# ramanPi_imagingBoard.net
KiCad netlist of a schematic drawn in EAGLE
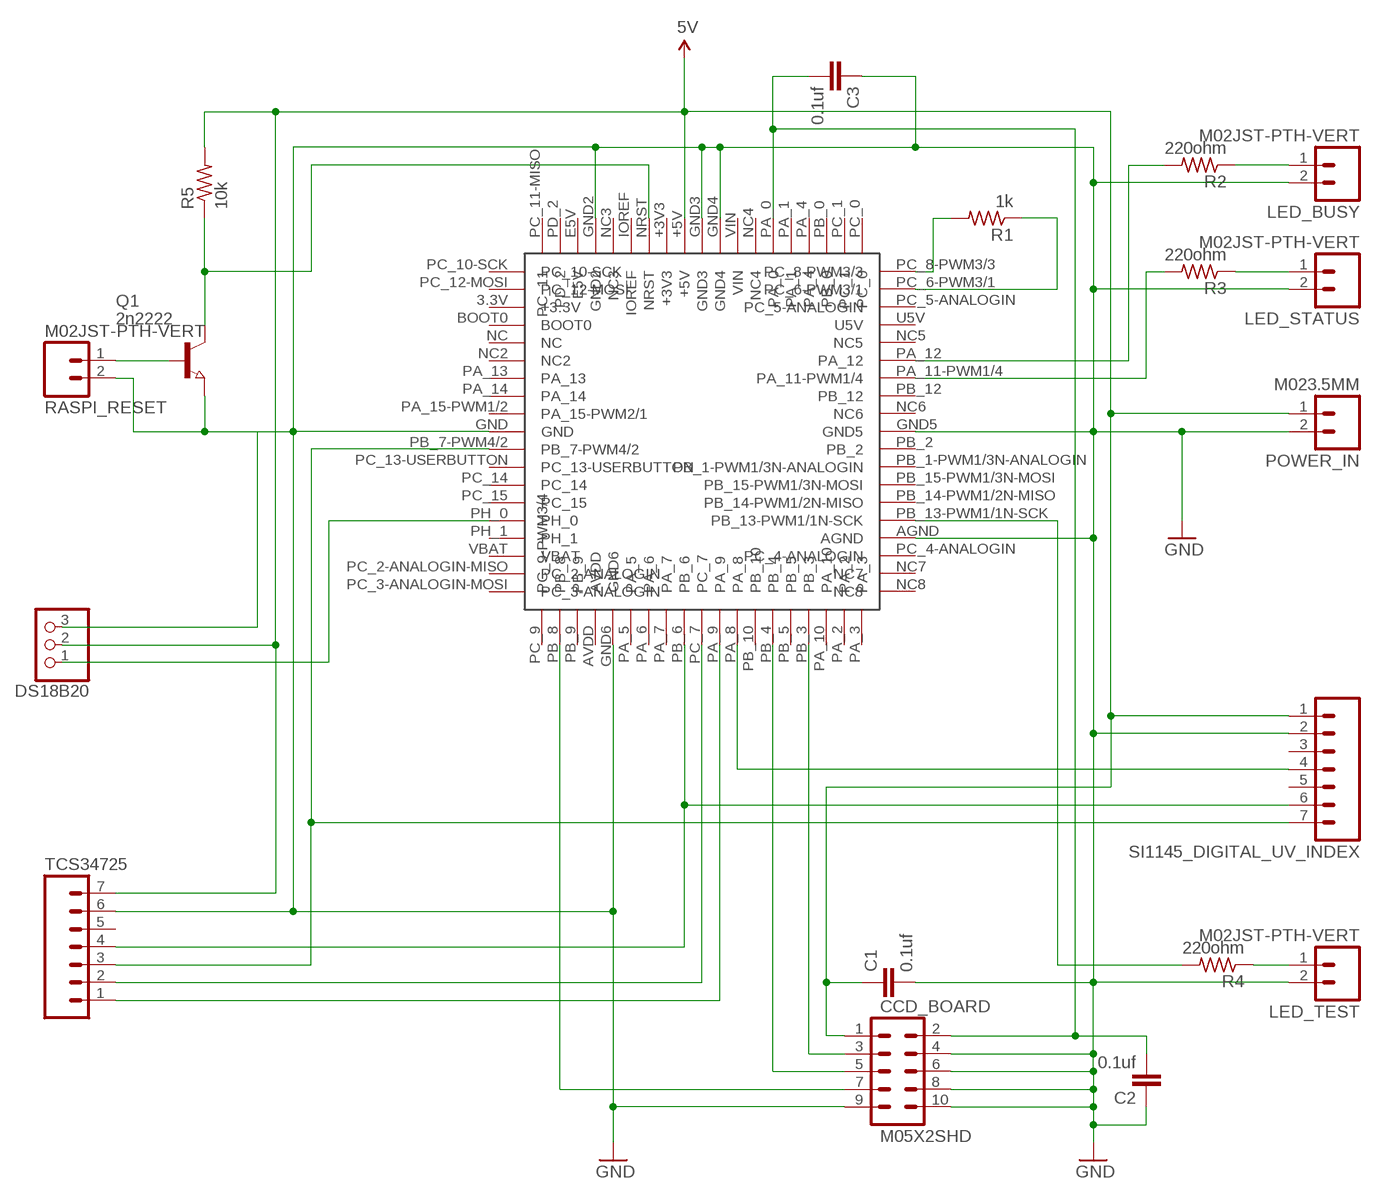
[diagram p0: schematic, sheet 1]

(export (version "E")
  (design (tool "Eeschema 10.0.6"))
  (components
    (comp (ref "C1")
      (value "0.1uf")
      (footprint "eagle-import:1210")
      (libsource (lib "eagle-import") (part "CAP1210"))
    )
    (comp (ref "C2")
      (value "0.1uf")
      (footprint "eagle-import:1210")
      (libsource (lib "eagle-import") (part "CAP1210"))
    )
    (comp (ref "C3")
      (value "0.1uf")
      (footprint "eagle-import:1210")
      (libsource (lib "eagle-import") (part "CAP1210"))
    )
    (comp (ref "CCD_BOARD")
      (value "M05X2SHD")
      (footprint "eagle-import:2X5-SHROUDED")
      (libsource (lib "eagle-import") (part "M05X2SHD"))
    )
    (comp (ref "DS18B20")
      (value "PINHD-1X3")
      (footprint "eagle-import:1X03")
      (libsource (lib "eagle-import") (part "PINHD-1X3"))
    )
    (comp (ref "LED_BUSY")
      (value "M02JST-PTH-VERT")
      (footprint "eagle-import:JST-2-PTH-VERT")
      (libsource (lib "eagle-import") (part "M02JST-PTH-VERT"))
    )
    (comp (ref "LED_STATUS")
      (value "M02JST-PTH-VERT")
      (footprint "eagle-import:JST-2-PTH-VERT")
      (libsource (lib "eagle-import") (part "M02JST-PTH-VERT"))
    )
    (comp (ref "LED_TEST")
      (value "M02JST-PTH-VERT")
      (footprint "eagle-import:JST-2-PTH-VERT")
      (libsource (lib "eagle-import") (part "M02JST-PTH-VERT"))
    )
    (comp (ref "POWER_IN")
      (value "M023.5MM")
      (footprint "eagle-import:SCREWTERMINAL-3.5MM-2")
      (libsource (lib "eagle-import") (part "M023.5MM"))
    )
    (comp (ref "Q1")
      (value "2n2222")
      (footprint "eagle-import:SOT23")
      (libsource (lib "eagle-import") (part "NPN-TRANSISTOR_SOT23"))
    )
    (comp (ref "R1")
      (value "1k")
      (footprint "eagle-import:M1206")
      (libsource (lib "eagle-import") (part "R-US_M1206"))
    )
    (comp (ref "R2")
      (value "220ohm")
      (footprint "eagle-import:M1206")
      (libsource (lib "eagle-import") (part "R-US_M1206"))
    )
    (comp (ref "R3")
      (value "220ohm")
      (footprint "eagle-import:M1206")
      (libsource (lib "eagle-import") (part "R-US_M1206"))
    )
    (comp (ref "R4")
      (value "220ohm")
      (footprint "eagle-import:M1206")
      (libsource (lib "eagle-import") (part "R-US_M1206"))
    )
    (comp (ref "R5")
      (value "10k")
      (footprint "eagle-import:M1206")
      (libsource (lib "eagle-import") (part "R-US_M1206"))
    )
    (comp (ref "RASPI_RESET")
      (value "M02JST-PTH-VERT")
      (footprint "eagle-import:JST-2-PTH-VERT")
      (libsource (lib "eagle-import") (part "M02JST-PTH-VERT"))
    )
    (comp (ref "SI1145_DIGITAL_UV_INDEX")
      (value "M07LOCK")
      (footprint "eagle-import:1X07_LOCK")
      (libsource (lib "eagle-import") (part "M07LOCK"))
    )
    (comp (ref "TCS34725")
      (value "M07")
      (footprint "eagle-import:1X07")
      (libsource (lib "eagle-import") (part "M07"))
    )
    (comp (ref "U$1")
      (value "STNUCLEOF401RE")
      (footprint "eagle-import:F401-RE")
      (libsource (lib "eagle-import") (part "STNUCLEOF401RE"))
    )
  )
  (nets
    (net (code "1") (name "/+3.3V") (class "Default")
      (node (ref "U$1") (pin "3.3V") (pinfunction "+3.3V_3.3V") (pintype "power_in"))
    )
    (net (code "2") (name "/+3V3") (class "Default")
      (node (ref "U$1") (pin "+3V3") (pinfunction "+3V3_+3V3") (pintype "power_in"))
    )
    (net (code "3") (name "/AVDD") (class "Default")
      (node (ref "U$1") (pin "AVDD") (pinfunction "AVDD_AVDD") (pintype "power_in"))
    )
    (net (code "4") (name "/E5V") (class "Default")
      (node (ref "U$1") (pin "E5V") (pinfunction "E5V_E5V") (pintype "power_in"))
    )
    (net (code "5") (name "/U5V") (class "Default")
      (node (ref "U$1") (pin "U5V") (pinfunction "U5V_U5V") (pintype "power_in"))
    )
    (net (code "6") (name "/VBAT") (class "Default")
      (node (ref "U$1") (pin "VBAT") (pinfunction "VBAT_VBAT") (pintype "power_in"))
    )
    (net (code "7") (name "/VIN") (class "Default")
      (node (ref "U$1") (pin "VIN") (pinfunction "VIN_VIN") (pintype "power_in"))
    )
    (net (code "8") (name "5V") (class "Default")
      (node (ref "C1") (pin "1") (pinfunction "1_1") (pintype "passive"))
      (node (ref "CCD_BOARD") (pin "1") (pinfunction "1_1") (pintype "passive"))
      (node (ref "DS18B20") (pin "2") (pinfunction "2_2") (pintype "passive"))
      (node (ref "POWER_IN") (pin "1") (pinfunction "1_1") (pintype "passive"))
      (node (ref "R5") (pin "2") (pinfunction "2_2") (pintype "passive"))
      (node (ref "SI1145_DIGITAL_UV_INDEX") (pin "1") (pinfunction "1_1") (pintype "passive"))
      (node (ref "TCS34725") (pin "7") (pinfunction "7_7") (pintype "passive"))
      (node (ref "U$1") (pin "+5V") (pinfunction "+5V_+5V") (pintype "power_in"))
    )
    (net (code "9") (name "GND") (class "Default")
      (node (ref "C1") (pin "2") (pinfunction "2_2") (pintype "passive"))
      (node (ref "C2") (pin "1") (pinfunction "1_1") (pintype "passive"))
      (node (ref "C3") (pin "1") (pinfunction "1_1") (pintype "passive"))
      (node (ref "CCD_BOARD") (pin "10") (pinfunction "10_10") (pintype "passive"))
      (node (ref "CCD_BOARD") (pin "4") (pinfunction "4_4") (pintype "passive"))
      (node (ref "CCD_BOARD") (pin "6") (pinfunction "6_6") (pintype "passive"))
      (node (ref "CCD_BOARD") (pin "8") (pinfunction "8_8") (pintype "passive"))
      (node (ref "CCD_BOARD") (pin "9") (pinfunction "9_9") (pintype "passive"))
      (node (ref "DS18B20") (pin "3") (pinfunction "3_3") (pintype "passive"))
      (node (ref "LED_BUSY") (pin "2") (pinfunction "2_2") (pintype "passive"))
      (node (ref "LED_STATUS") (pin "2") (pinfunction "2_2") (pintype "passive"))
      (node (ref "LED_TEST") (pin "2") (pinfunction "2_2") (pintype "passive"))
      (node (ref "POWER_IN") (pin "2") (pinfunction "2_2") (pintype "passive"))
      (node (ref "Q1") (pin "2") (pinfunction "E_2") (pintype "passive"))
      (node (ref "RASPI_RESET") (pin "2") (pinfunction "2_2") (pintype "passive"))
      (node (ref "SI1145_DIGITAL_UV_INDEX") (pin "2") (pinfunction "2_2") (pintype "passive"))
      (node (ref "TCS34725") (pin "6") (pinfunction "6_6") (pintype "passive"))
      (node (ref "U$1") (pin "AGND") (pinfunction "AGND_AGND") (pintype "power_in"))
      (node (ref "U$1") (pin "GND") (pinfunction "GND_GND") (pintype "power_in"))
      (node (ref "U$1") (pin "GND2") (pinfunction "GND2_GND2") (pintype "power_in"))
      (node (ref "U$1") (pin "GND3") (pinfunction "GND3_GND3") (pintype "power_in"))
      (node (ref "U$1") (pin "GND4") (pinfunction "GND4_GND4") (pintype "power_in"))
      (node (ref "U$1") (pin "GND5") (pinfunction "GND5_GND5") (pintype "power_in"))
      (node (ref "U$1") (pin "GND6") (pinfunction "GND6_GND6") (pintype "power_in"))
    )
    (net (code "10") (name "Net-(C2-Pad2)") (class "Default")
      (node (ref "C2") (pin "2") (pinfunction "2_2") (pintype "passive"))
      (node (ref "C3") (pin "2") (pinfunction "2_2") (pintype "passive"))
      (node (ref "CCD_BOARD") (pin "2") (pinfunction "2_2") (pintype "passive"))
      (node (ref "U$1") (pin "PA_0") (pinfunction "PA_0_PA_0") (pintype "bidirectional"))
    )
    (net (code "11") (name "Net-(CCD_BOARD-Pad3)") (class "Default")
      (node (ref "CCD_BOARD") (pin "3") (pinfunction "3_3") (pintype "passive"))
      (node (ref "U$1") (pin "PB_3") (pinfunction "PB_3_PB_3") (pintype "bidirectional"))
    )
    (net (code "12") (name "Net-(CCD_BOARD-Pad5)") (class "Default")
      (node (ref "CCD_BOARD") (pin "5") (pinfunction "5_5") (pintype "passive"))
      (node (ref "U$1") (pin "PB_4") (pinfunction "PB_4_PB_4") (pintype "bidirectional"))
    )
    (net (code "13") (name "Net-(CCD_BOARD-Pad7)") (class "Default")
      (node (ref "CCD_BOARD") (pin "7") (pinfunction "7_7") (pintype "passive"))
      (node (ref "U$1") (pin "PB_8") (pinfunction "PB_8_PB_8") (pintype "bidirectional"))
    )
    (net (code "14") (name "Net-(DS18B20-Pad1)") (class "Default")
      (node (ref "DS18B20") (pin "1") (pinfunction "1_1") (pintype "passive"))
      (node (ref "U$1") (pin "PH_0") (pinfunction "PH_0_PH_0") (pintype "bidirectional"))
    )
    (net (code "15") (name "Net-(LED_BUSY-Pad1)") (class "Default")
      (node (ref "LED_BUSY") (pin "1") (pinfunction "1_1") (pintype "passive"))
      (node (ref "R2") (pin "1") (pinfunction "1_1") (pintype "passive"))
    )
    (net (code "16") (name "Net-(LED_STATUS-Pad1)") (class "Default")
      (node (ref "LED_STATUS") (pin "1") (pinfunction "1_1") (pintype "passive"))
      (node (ref "R3") (pin "1") (pinfunction "1_1") (pintype "passive"))
    )
    (net (code "17") (name "Net-(LED_TEST-Pad1)") (class "Default")
      (node (ref "LED_TEST") (pin "1") (pinfunction "1_1") (pintype "passive"))
      (node (ref "R4") (pin "1") (pinfunction "1_1") (pintype "passive"))
    )
    (net (code "18") (name "Net-(Q1-B)") (class "Default")
      (node (ref "Q1") (pin "1") (pinfunction "B_1") (pintype "passive"))
      (node (ref "RASPI_RESET") (pin "1") (pinfunction "1_1") (pintype "passive"))
    )
    (net (code "19") (name "Net-(Q1-C)") (class "Default")
      (node (ref "Q1") (pin "3") (pinfunction "C_3") (pintype "passive"))
      (node (ref "R5") (pin "1") (pinfunction "1_1") (pintype "passive"))
      (node (ref "U$1") (pin "NRST") (pinfunction "NRST_NRST") (pintype "bidirectional"))
    )
    (net (code "20") (name "Net-(R1-Pad1)") (class "Default")
      (node (ref "R1") (pin "1") (pinfunction "1_1") (pintype "passive"))
      (node (ref "U$1") (pin "PC_6-PWM3/1") (pinfunction "PC_6-PWM3/1_PC_6-PWM3/1") (pintype "bidirectional"))
    )
    (net (code "21") (name "Net-(R1-Pad2)") (class "Default")
      (node (ref "R1") (pin "2") (pinfunction "2_2") (pintype "passive"))
      (node (ref "U$1") (pin "PC_8-PWM3/3") (pinfunction "PC_8-PWM3/3_PC_8-PWM3/3") (pintype "bidirectional"))
    )
    (net (code "22") (name "Net-(R2-Pad2)") (class "Default")
      (node (ref "R2") (pin "2") (pinfunction "2_2") (pintype "passive"))
      (node (ref "U$1") (pin "PA_12") (pinfunction "PA_12_PA_12") (pintype "bidirectional"))
    )
    (net (code "23") (name "Net-(R3-Pad2)") (class "Default")
      (node (ref "R3") (pin "2") (pinfunction "2_2") (pintype "passive"))
      (node (ref "U$1") (pin "PA_11-PWM1/4") (pinfunction "PA_11-PWM1/4_PA_11-PWM1/4") (pintype "bidirectional"))
    )
    (net (code "24") (name "Net-(R4-Pad2)") (class "Default")
      (node (ref "R4") (pin "2") (pinfunction "2_2") (pintype "passive"))
      (node (ref "U$1") (pin "PB_13-PWM1/1N-SCK") (pinfunction "PB_13-PWM1/1N-SCK_PB_13-PWM1/1N-SCK") (pintype "bidirectional"))
    )
    (net (code "25") (name "Net-(SI1145_DIGITAL_UV_INDEX-Pad4)") (class "Default")
      (node (ref "SI1145_DIGITAL_UV_INDEX") (pin "4") (pinfunction "4_4") (pintype "passive"))
      (node (ref "U$1") (pin "PA_8") (pinfunction "PA_8_PA_8") (pintype "bidirectional"))
    )
    (net (code "26") (name "Net-(SI1145_DIGITAL_UV_INDEX-Pad6)") (class "Default")
      (node (ref "SI1145_DIGITAL_UV_INDEX") (pin "6") (pinfunction "6_6") (pintype "passive"))
      (node (ref "TCS34725") (pin "4") (pinfunction "4_4") (pintype "passive"))
      (node (ref "U$1") (pin "PB_6") (pinfunction "PB_6_PB_6") (pintype "bidirectional"))
    )
    (net (code "27") (name "Net-(SI1145_DIGITAL_UV_INDEX-Pad7)") (class "Default")
      (node (ref "SI1145_DIGITAL_UV_INDEX") (pin "7") (pinfunction "7_7") (pintype "passive"))
      (node (ref "TCS34725") (pin "3") (pinfunction "3_3") (pintype "passive"))
      (node (ref "U$1") (pin "PB_7-PWM4/2") (pinfunction "PB_7-PWM4/2_PB_7-PWM4/2") (pintype "bidirectional"))
    )
    (net (code "28") (name "Net-(TCS34725-Pad1)") (class "Default")
      (node (ref "TCS34725") (pin "1") (pinfunction "1_1") (pintype "passive"))
      (node (ref "U$1") (pin "PA_9") (pinfunction "PA_9_PA_9") (pintype "bidirectional"))
    )
    (net (code "29") (name "Net-(TCS34725-Pad2)") (class "Default")
      (node (ref "TCS34725") (pin "2") (pinfunction "2_2") (pintype "passive"))
      (node (ref "U$1") (pin "PC_7") (pinfunction "PC_7_PC_7") (pintype "bidirectional"))
    )
    (net (code "30") (name "unconnected-(SI1145_DIGITAL_UV_INDEX-Pad3)") (class "Default")
      (node (ref "SI1145_DIGITAL_UV_INDEX") (pin "3") (pinfunction "3_3") (pintype "passive"))
    )
    (net (code "31") (name "unconnected-(SI1145_DIGITAL_UV_INDEX-Pad5)") (class "Default")
      (node (ref "SI1145_DIGITAL_UV_INDEX") (pin "5") (pinfunction "5_5") (pintype "passive"))
    )
    (net (code "32") (name "unconnected-(TCS34725-Pad5)") (class "Default")
      (node (ref "TCS34725") (pin "5") (pinfunction "5_5") (pintype "passive"))
    )
    (net (code "33") (name "unconnected-(U$1-PA_15-PWM2{slash}1-PadPA_15-PWM1{slash}2)") (class "Default")
      (node (ref "U$1") (pin "PA_15-PWM1/2") (pinfunction "PA_15-PWM2/1_PA_15-PWM1/2") (pintype "bidirectional"))
    )
    (net (code "34") (name "unconnected-(U$1-PC_2-ANALOGIN-PadPC_2-ANALOGIN-MISO)") (class "Default")
      (node (ref "U$1") (pin "PC_2-ANALOGIN-MISO") (pinfunction "PC_2-ANALOGIN_PC_2-ANALOGIN-MISO") (pintype "bidirectional"))
    )
    (net (code "35") (name "unconnected-(U$1-PC_3-ANALOGIN-PadPC_3-ANALOGIN-MOSI)") (class "Default")
      (node (ref "U$1") (pin "PC_3-ANALOGIN-MOSI") (pinfunction "PC_3-ANALOGIN_PC_3-ANALOGIN-MOSI") (pintype "bidirectional"))
    )
    (net (code "36") (name "unconnected-(U$1-PC_9-PWM3{slash}4-PadPC_9)") (class "Default")
      (node (ref "U$1") (pin "PC_9") (pinfunction "PC_9-PWM3/4_PC_9") (pintype "bidirectional"))
    )
    (net (code "37") (name "unconnected-(U$1-PC_11-PadPC_11-MISO)") (class "Default")
      (node (ref "U$1") (pin "PC_11-MISO") (pinfunction "PC_11_PC_11-MISO") (pintype "bidirectional"))
    )
    (net (code "38") (name "unconnected-(U$1-PadBOOT0)") (class "Default")
      (node (ref "U$1") (pin "BOOT0") (pinfunction "BOOT0_BOOT0") (pintype "bidirectional"))
    )
    (net (code "39") (name "unconnected-(U$1-PadIOREF)") (class "Default")
      (node (ref "U$1") (pin "IOREF") (pinfunction "IOREF_IOREF") (pintype "bidirectional"))
    )
    (net (code "40") (name "unconnected-(U$1-PadNC)") (class "Default")
      (node (ref "U$1") (pin "NC") (pinfunction "NC_NC") (pintype "no_connect"))
    )
    (net (code "41") (name "unconnected-(U$1-PadNC2)") (class "Default")
      (node (ref "U$1") (pin "NC2") (pinfunction "NC2_NC2") (pintype "no_connect"))
    )
    (net (code "42") (name "unconnected-(U$1-PadNC3)") (class "Default")
      (node (ref "U$1") (pin "NC3") (pinfunction "NC3_NC3") (pintype "no_connect"))
    )
    (net (code "43") (name "unconnected-(U$1-PadNC4)") (class "Default")
      (node (ref "U$1") (pin "NC4") (pinfunction "NC4_NC4") (pintype "bidirectional"))
    )
    (net (code "44") (name "unconnected-(U$1-PadNC5)") (class "Default")
      (node (ref "U$1") (pin "NC5") (pinfunction "NC5_NC5") (pintype "no_connect"))
    )
    (net (code "45") (name "unconnected-(U$1-PadNC6)") (class "Default")
      (node (ref "U$1") (pin "NC6") (pinfunction "NC6_NC6") (pintype "no_connect"))
    )
    (net (code "46") (name "unconnected-(U$1-PadNC7)") (class "Default")
      (node (ref "U$1") (pin "NC7") (pinfunction "NC7_NC7") (pintype "bidirectional"))
    )
    (net (code "47") (name "unconnected-(U$1-PadNC8)") (class "Default")
      (node (ref "U$1") (pin "NC8") (pinfunction "NC8_NC8") (pintype "bidirectional"))
    )
    (net (code "48") (name "unconnected-(U$1-PadPA_1)") (class "Default")
      (node (ref "U$1") (pin "PA_1") (pinfunction "PA_1_PA_1") (pintype "bidirectional"))
    )
    (net (code "49") (name "unconnected-(U$1-PadPA_2)") (class "Default")
      (node (ref "U$1") (pin "PA_2") (pinfunction "PA_2_PA_2") (pintype "bidirectional"))
    )
    (net (code "50") (name "unconnected-(U$1-PadPA_3)") (class "Default")
      (node (ref "U$1") (pin "PA_3") (pinfunction "PA_3_PA_3") (pintype "bidirectional"))
    )
    (net (code "51") (name "unconnected-(U$1-PadPA_4)") (class "Default")
      (node (ref "U$1") (pin "PA_4") (pinfunction "PA_4_PA_4") (pintype "bidirectional"))
    )
    (net (code "52") (name "unconnected-(U$1-PadPA_5)") (class "Default")
      (node (ref "U$1") (pin "PA_5") (pinfunction "PA_5_PA_5") (pintype "bidirectional"))
    )
    (net (code "53") (name "unconnected-(U$1-PadPA_6)") (class "Default")
      (node (ref "U$1") (pin "PA_6") (pinfunction "PA_6_PA_6") (pintype "bidirectional"))
    )
    (net (code "54") (name "unconnected-(U$1-PadPA_7)") (class "Default")
      (node (ref "U$1") (pin "PA_7") (pinfunction "PA_7_PA_7") (pintype "bidirectional"))
    )
    (net (code "55") (name "unconnected-(U$1-PadPA_10)") (class "Default")
      (node (ref "U$1") (pin "PA_10") (pinfunction "PA_10_PA_10") (pintype "bidirectional"))
    )
    (net (code "56") (name "unconnected-(U$1-PadPA_13)") (class "Default")
      (node (ref "U$1") (pin "PA_13") (pinfunction "PA_13_PA_13") (pintype "bidirectional"))
    )
    (net (code "57") (name "unconnected-(U$1-PadPA_14)") (class "Default")
      (node (ref "U$1") (pin "PA_14") (pinfunction "PA_14_PA_14") (pintype "bidirectional"))
    )
    (net (code "58") (name "unconnected-(U$1-PadPB_0)") (class "Default")
      (node (ref "U$1") (pin "PB_0") (pinfunction "PB_0_PB_0") (pintype "bidirectional"))
    )
    (net (code "59") (name "unconnected-(U$1-PadPB_1-PWM1{slash}3N-ANALOGIN)") (class "Default")
      (node (ref "U$1") (pin "PB_1-PWM1/3N-ANALOGIN") (pinfunction "PB_1-PWM1/3N-ANALOGIN_PB_1-PWM1/3N-ANALOGIN") (pintype "bidirectional"))
    )
    (net (code "60") (name "unconnected-(U$1-PadPB_2)") (class "Default")
      (node (ref "U$1") (pin "PB_2") (pinfunction "PB_2_PB_2") (pintype "bidirectional"))
    )
    (net (code "61") (name "unconnected-(U$1-PadPB_5)") (class "Default")
      (node (ref "U$1") (pin "PB_5") (pinfunction "PB_5_PB_5") (pintype "bidirectional"))
    )
    (net (code "62") (name "unconnected-(U$1-PadPB_9)") (class "Default")
      (node (ref "U$1") (pin "PB_9") (pinfunction "PB_9_PB_9") (pintype "bidirectional"))
    )
    (net (code "63") (name "unconnected-(U$1-PadPB_10)") (class "Default")
      (node (ref "U$1") (pin "PB_10") (pinfunction "PB_10_PB_10") (pintype "bidirectional"))
    )
    (net (code "64") (name "unconnected-(U$1-PadPB_12)") (class "Default")
      (node (ref "U$1") (pin "PB_12") (pinfunction "PB_12_PB_12") (pintype "bidirectional"))
    )
    (net (code "65") (name "unconnected-(U$1-PadPB_14-PWM1{slash}2N-MISO)") (class "Default")
      (node (ref "U$1") (pin "PB_14-PWM1/2N-MISO") (pinfunction "PB_14-PWM1/2N-MISO_PB_14-PWM1/2N-MISO") (pintype "bidirectional"))
    )
    (net (code "66") (name "unconnected-(U$1-PadPB_15-PWM1{slash}3N-MOSI)") (class "Default")
      (node (ref "U$1") (pin "PB_15-PWM1/3N-MOSI") (pinfunction "PB_15-PWM1/3N-MOSI_PB_15-PWM1/3N-MOSI") (pintype "bidirectional"))
    )
    (net (code "67") (name "unconnected-(U$1-PadPC_0)") (class "Default")
      (node (ref "U$1") (pin "PC_0") (pinfunction "PC_0_PC_0") (pintype "bidirectional"))
    )
    (net (code "68") (name "unconnected-(U$1-PadPC_1)") (class "Default")
      (node (ref "U$1") (pin "PC_1") (pinfunction "PC_1_PC_1") (pintype "bidirectional"))
    )
    (net (code "69") (name "unconnected-(U$1-PadPC_4-ANALOGIN)") (class "Default")
      (node (ref "U$1") (pin "PC_4-ANALOGIN") (pinfunction "PC_4-ANALOGIN_PC_4-ANALOGIN") (pintype "bidirectional"))
    )
    (net (code "70") (name "unconnected-(U$1-PadPC_5-ANALOGIN)") (class "Default")
      (node (ref "U$1") (pin "PC_5-ANALOGIN") (pinfunction "PC_5-ANALOGIN_PC_5-ANALOGIN") (pintype "bidirectional"))
    )
    (net (code "71") (name "unconnected-(U$1-PadPC_10-SCK)") (class "Default")
      (node (ref "U$1") (pin "PC_10-SCK") (pinfunction "PC_10-SCK_PC_10-SCK") (pintype "bidirectional"))
    )
    (net (code "72") (name "unconnected-(U$1-PadPC_12-MOSI)") (class "Default")
      (node (ref "U$1") (pin "PC_12-MOSI") (pinfunction "PC_12-MOSI_PC_12-MOSI") (pintype "bidirectional"))
    )
    (net (code "73") (name "unconnected-(U$1-PadPC_13-USERBUTTON)") (class "Default")
      (node (ref "U$1") (pin "PC_13-USERBUTTON") (pinfunction "PC_13-USERBUTTON_PC_13-USERBUTTON") (pintype "bidirectional"))
    )
    (net (code "74") (name "unconnected-(U$1-PadPC_14)") (class "Default")
      (node (ref "U$1") (pin "PC_14") (pinfunction "PC_14_PC_14") (pintype "bidirectional"))
    )
    (net (code "75") (name "unconnected-(U$1-PadPC_15)") (class "Default")
      (node (ref "U$1") (pin "PC_15") (pinfunction "PC_15_PC_15") (pintype "bidirectional"))
    )
    (net (code "76") (name "unconnected-(U$1-PadPD_2)") (class "Default")
      (node (ref "U$1") (pin "PD_2") (pinfunction "PD_2_PD_2") (pintype "bidirectional"))
    )
    (net (code "77") (name "unconnected-(U$1-PadPH_1)") (class "Default")
      (node (ref "U$1") (pin "PH_1") (pinfunction "PH_1_PH_1") (pintype "bidirectional"))
    )
  )
)
